# PROB_S7CAS_FLASH-JTAG.net
KiCad netlist of a schematic drawn in Altium Designer
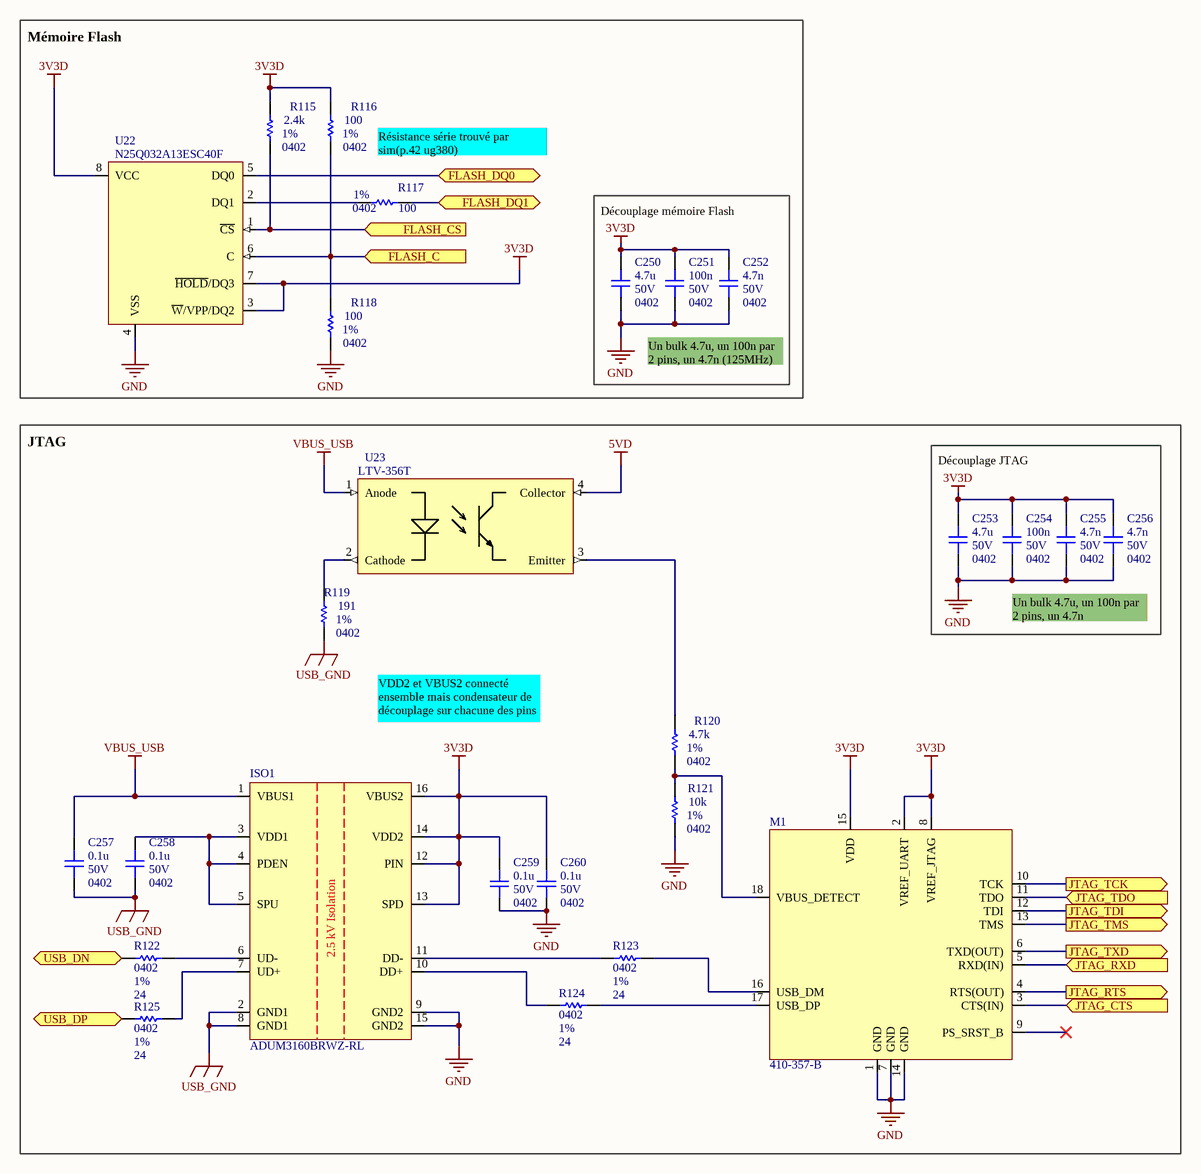
[diagram p0: PROB_S7CAS_FLASH-JTAG.SchDoc]

(export (version "E")
  (design (tool "Eeschema 10.0.6"))
  (components
    (comp (ref "C250")
      (value "4.7u")
      (footprint "CAP_0402")
      (description "CAP - 0402")
      (fields
        (field (name "VOLTAGE") "50V")
        (field (name "PACKAGE") "0402")
        (field (name "CREATEDBY") "Jonathan Bouchard")
      )
      (libsource (lib "S7CAS_LIB2021") (part "CAP - 0402"))
    )
    (comp (ref "C251")
      (value "100n")
      (footprint "CAP_0402")
      (description "CAP - 0402")
      (fields
        (field (name "VOLTAGE") "50V")
        (field (name "PACKAGE") "0402")
        (field (name "CREATEDBY") "Jonathan Bouchard")
      )
      (libsource (lib "S7CAS_LIB2021") (part "CAP - 0402"))
    )
    (comp (ref "C252")
      (value "4.7n")
      (footprint "CAP_0402")
      (description "CAP - 0402")
      (fields
        (field (name "VOLTAGE") "50V")
        (field (name "PACKAGE") "0402")
        (field (name "CREATEDBY") "Jonathan Bouchard")
      )
      (libsource (lib "S7CAS_LIB2021") (part "CAP - 0402"))
    )
    (comp (ref "C253")
      (value "4.7u")
      (footprint "CAP_0402")
      (description "CAP - 0402")
      (fields
        (field (name "VOLTAGE") "50V")
        (field (name "PACKAGE") "0402")
        (field (name "CREATEDBY") "Jonathan Bouchard")
      )
      (libsource (lib "S7CAS_LIB2021") (part "CAP - 0402"))
    )
    (comp (ref "C254")
      (value "100n")
      (footprint "CAP_0402")
      (description "CAP - 0402")
      (fields
        (field (name "VOLTAGE") "50V")
        (field (name "PACKAGE") "0402")
        (field (name "CREATEDBY") "Jonathan Bouchard")
      )
      (libsource (lib "S7CAS_LIB2021") (part "CAP - 0402"))
    )
    (comp (ref "C255")
      (value "4.7n")
      (footprint "CAP_0402")
      (description "CAP - 0402")
      (fields
        (field (name "VOLTAGE") "50V")
        (field (name "PACKAGE") "0402")
        (field (name "CREATEDBY") "Jonathan Bouchard")
      )
      (libsource (lib "S7CAS_LIB2021") (part "CAP - 0402"))
    )
    (comp (ref "C256")
      (value "4.7n")
      (footprint "CAP_0402")
      (description "CAP - 0402")
      (fields
        (field (name "VOLTAGE") "50V")
        (field (name "PACKAGE") "0402")
        (field (name "CREATEDBY") "Jonathan Bouchard")
      )
      (libsource (lib "S7CAS_LIB2021") (part "CAP - 0402"))
    )
    (comp (ref "C257")
      (value "0.1u")
      (footprint "CAP_0402")
      (description "CAP - 0402")
      (fields
        (field (name "VOLTAGE") "50V")
        (field (name "PACKAGE") "0402")
        (field (name "CREATEDBY") "Jonathan Bouchard")
      )
      (libsource (lib "S7CAS_LIB2021") (part "CAP - 0402"))
    )
    (comp (ref "C258")
      (value "0.1u")
      (footprint "CAP_0402")
      (description "CAP - 0402")
      (fields
        (field (name "VOLTAGE") "50V")
        (field (name "PACKAGE") "0402")
        (field (name "CREATEDBY") "Jonathan Bouchard")
      )
      (libsource (lib "S7CAS_LIB2021") (part "CAP - 0402"))
    )
    (comp (ref "C259")
      (value "0.1u")
      (footprint "CAP_0402")
      (description "CAP - 0402")
      (fields
        (field (name "VOLTAGE") "50V")
        (field (name "PACKAGE") "0402")
        (field (name "CREATEDBY") "Jonathan Bouchard")
      )
      (libsource (lib "S7CAS_LIB2021") (part "CAP - 0402"))
    )
    (comp (ref "C260")
      (value "0.1u")
      (footprint "CAP_0402")
      (description "CAP - 0402")
      (fields
        (field (name "VOLTAGE") "50V")
        (field (name "PACKAGE") "0402")
        (field (name "CREATEDBY") "Jonathan Bouchard")
      )
      (libsource (lib "S7CAS_LIB2021") (part "CAP - 0402"))
    )
    (comp (ref "ISO1")
      (value "ADUM3160BRWZ-RL")
      (footprint "ISO_ADUM3160BRWZ-RL")
      (description "ISO - DGTL ISO 2.5KV 2CH USB - 16SOIC")
      (fields
        (field (name "CREATEDBY/DATE") "Tommy Rossignol 2018-11-16")
        (field (name "VERIFIEDBY") "Caroline Paulin - 13 février 2019")
      )
      (libsource (lib "S7CAS_LIB2021") (part "ISO_ADUM3160BRWZ-RL"))
    )
    (comp (ref "M1")
      (value "410-357-B")
      (footprint "MOD_JTAG_410-357-B")
      (description "MOD - JTAG-SMT3-NC Programming Module For Xilinx FPGA - 18-SMT")
      (fields
        (field (name "CREATEDBY/DATE") "Tommy Rossignol 2018-11-23")
        (field (name "VERIFIEDBY") "Nicolas V. (2019-01-28)")
      )
      (libsource (lib "S7CAS_LIB2021") (part "MOD_JTAG_410-357-B"))
    )
    (comp (ref "R115")
      (value "2.4k")
      (footprint "RES_0402")
      (description "RES - 0402")
      (fields
        (field (name "VOLTAGE") "50V")
        (field (name "POWER") "1/16W")
        (field (name "PACKAGE") "0402")
        (field (name "PRECISION") "1%")
        (field (name "CREATEDBY") "Jonathan Bouchard")
      )
      (libsource (lib "S7CAS_LIB2021") (part "RES - 0402"))
    )
    (comp (ref "R116")
      (value "100")
      (footprint "RES_0402")
      (description "RES - 0402")
      (fields
        (field (name "VOLTAGE") "50V")
        (field (name "POWER") "1/16W")
        (field (name "PACKAGE") "0402")
        (field (name "PRECISION") "1%")
        (field (name "CREATEDBY") "Jonathan Bouchard")
      )
      (libsource (lib "S7CAS_LIB2021") (part "RES - 0402"))
    )
    (comp (ref "R117")
      (value "100")
      (footprint "RES_0402")
      (description "RES - 0402")
      (fields
        (field (name "VOLTAGE") "50V")
        (field (name "POWER") "1/16W")
        (field (name "PACKAGE") "0402")
        (field (name "PRECISION") "1%")
        (field (name "CREATEDBY") "Jonathan Bouchard")
      )
      (libsource (lib "S7CAS_LIB2021") (part "RES - 0402"))
    )
    (comp (ref "R118")
      (value "100")
      (footprint "RES_0402")
      (description "RES - 0402")
      (fields
        (field (name "VOLTAGE") "50V")
        (field (name "POWER") "1/16W")
        (field (name "PACKAGE") "0402")
        (field (name "PRECISION") "1%")
        (field (name "CREATEDBY") "Jonathan Bouchard")
      )
      (libsource (lib "S7CAS_LIB2021") (part "RES - 0402"))
    )
    (comp (ref "R119")
      (value "191")
      (footprint "RES_0402")
      (description "RES - 0402")
      (fields
        (field (name "VOLTAGE") "50V")
        (field (name "POWER") "1/16W")
        (field (name "PACKAGE") "0402")
        (field (name "PRECISION") "1%")
        (field (name "CREATEDBY") "Jonathan Bouchard")
      )
      (libsource (lib "S7CAS_LIB2021") (part "RES - 0402"))
    )
    (comp (ref "R120")
      (value "4.7k")
      (footprint "RES_0402")
      (description "RES - 0402")
      (fields
        (field (name "VOLTAGE") "50V")
        (field (name "POWER") "1/16W")
        (field (name "PACKAGE") "0402")
        (field (name "PRECISION") "1%")
        (field (name "CREATEDBY") "Jonathan Bouchard")
      )
      (libsource (lib "S7CAS_LIB2021") (part "RES - 0402"))
    )
    (comp (ref "R121")
      (value "10k")
      (footprint "RES_0402")
      (description "RES - 0402")
      (fields
        (field (name "VOLTAGE") "50V")
        (field (name "POWER") "1/16W")
        (field (name "PACKAGE") "0402")
        (field (name "PRECISION") "1%")
        (field (name "CREATEDBY") "Jonathan Bouchard")
      )
      (libsource (lib "S7CAS_LIB2021") (part "RES - 0402"))
    )
    (comp (ref "R122")
      (value "24")
      (footprint "RES_0402")
      (description "RES - 0402")
      (fields
        (field (name "VOLTAGE") "50V")
        (field (name "POWER") "1/16W")
        (field (name "PACKAGE") "0402")
        (field (name "PRECISION") "1%")
        (field (name "CREATEDBY") "Jonathan Bouchard")
      )
      (libsource (lib "S7CAS_LIB2021") (part "RES - 0402"))
    )
    (comp (ref "R123")
      (value "24")
      (footprint "RES_0402")
      (description "RES - 0402")
      (fields
        (field (name "VOLTAGE") "50V")
        (field (name "POWER") "1/16W")
        (field (name "PACKAGE") "0402")
        (field (name "PRECISION") "1%")
        (field (name "CREATEDBY") "Jonathan Bouchard")
      )
      (libsource (lib "S7CAS_LIB2021") (part "RES - 0402"))
    )
    (comp (ref "R124")
      (value "24")
      (footprint "RES_0402")
      (description "RES - 0402")
      (fields
        (field (name "VOLTAGE") "50V")
        (field (name "POWER") "1/16W")
        (field (name "PACKAGE") "0402")
        (field (name "PRECISION") "1%")
        (field (name "CREATEDBY") "Jonathan Bouchard")
      )
      (libsource (lib "S7CAS_LIB2021") (part "RES - 0402"))
    )
    (comp (ref "R125")
      (value "24")
      (footprint "RES_0402")
      (description "RES - 0402")
      (fields
        (field (name "VOLTAGE") "50V")
        (field (name "POWER") "1/16W")
        (field (name "PACKAGE") "0402")
        (field (name "PRECISION") "1%")
        (field (name "CREATEDBY") "Jonathan Bouchard")
      )
      (libsource (lib "S7CAS_LIB2021") (part "RES - 0402"))
    )
    (comp (ref "U22")
      (value "N25Q032A13ESC40F")
      (footprint "SOIC127P790X216-8N")
      (description "N25Q032A - 32Mb, 3V, Multiple I/O Serial Flash Memory - 8-SOIC (0.209\", 5.30mm Width)")
      (libsource (lib "LIB_TEMP_S7CAS_SCH") (part "IC FLASH 32MBIT SPI 108MHZ 8SO"))
    )
    (comp (ref "U23")
      (value "LTV-356T")
      (footprint "SOP254P700X240-4N")
      (description "LTV-356T - OPTOISOLATOR 3.75KV TRANS - 4-SOP")
      (libsource (lib "LIB_TEMP_S7CAS_SCH") (part "LTV-356T"))
    )
  )
  (nets
    (net (code "1") (name "/FLASH_C") (class "Default")
      (node (ref "R116") (pin "1") (pinfunction "1_1") (pintype "passive"))
      (node (ref "R118") (pin "2") (pinfunction "2_2") (pintype "passive"))
      (node (ref "U22") (pin "6") (pinfunction "C_6") (pintype "input"))
    )
    (net (code "2") (name "/FLASH_CS") (class "Default")
      (node (ref "R115") (pin "1") (pinfunction "1_1") (pintype "passive"))
      (node (ref "U22") (pin "1") (pinfunction "~{CS}_1") (pintype "input"))
    )
    (net (code "3") (name "/FLASH_DQ0") (class "Default")
      (node (ref "U22") (pin "5") (pinfunction "DQ0_5") (pintype "bidirectional"))
    )
    (net (code "4") (name "/FLASH_DQ1") (class "Default")
      (node (ref "R117") (pin "2") (pinfunction "2_2") (pintype "passive"))
    )
    (net (code "5") (name "/JTAG_CTS") (class "Default")
      (node (ref "M1") (pin "3") (pinfunction "CTS(IN)_3") (pintype "passive"))
    )
    (net (code "6") (name "/JTAG_RTS") (class "Default")
      (node (ref "M1") (pin "4") (pinfunction "RTS(OUT)_4") (pintype "passive"))
    )
    (net (code "7") (name "/JTAG_RXD") (class "Default")
      (node (ref "M1") (pin "5") (pinfunction "RXD(IN)_5") (pintype "passive"))
    )
    (net (code "8") (name "/JTAG_TCK") (class "Default")
      (node (ref "M1") (pin "10") (pinfunction "TCK_10") (pintype "passive"))
    )
    (net (code "9") (name "/JTAG_TDI") (class "Default")
      (node (ref "M1") (pin "12") (pinfunction "TDI_12") (pintype "passive"))
    )
    (net (code "10") (name "/JTAG_TDO") (class "Default")
      (node (ref "M1") (pin "11") (pinfunction "TDO_11") (pintype "passive"))
    )
    (net (code "11") (name "/JTAG_TMS") (class "Default")
      (node (ref "M1") (pin "13") (pinfunction "TMS_13") (pintype "passive"))
    )
    (net (code "12") (name "/JTAG_TXD") (class "Default")
      (node (ref "M1") (pin "6") (pinfunction "TXD(OUT)_6") (pintype "passive"))
    )
    (net (code "13") (name "/USB_DN") (class "Default")
      (node (ref "R122") (pin "2") (pinfunction "2_2") (pintype "passive"))
    )
    (net (code "14") (name "/USB_DP") (class "Default")
      (node (ref "R125") (pin "2") (pinfunction "2_2") (pintype "passive"))
    )
    (net (code "15") (name "3V3D") (class "Default")
      (node (ref "C250") (pin "2") (pinfunction "2_2") (pintype "passive"))
      (node (ref "C251") (pin "2") (pinfunction "2_2") (pintype "passive"))
      (node (ref "C252") (pin "2") (pinfunction "2_2") (pintype "passive"))
      (node (ref "C253") (pin "2") (pinfunction "2_2") (pintype "passive"))
      (node (ref "C254") (pin "2") (pinfunction "2_2") (pintype "passive"))
      (node (ref "C255") (pin "2") (pinfunction "2_2") (pintype "passive"))
      (node (ref "C256") (pin "2") (pinfunction "2_2") (pintype "passive"))
      (node (ref "C259") (pin "2") (pinfunction "2_2") (pintype "passive"))
      (node (ref "C260") (pin "2") (pinfunction "2_2") (pintype "passive"))
      (node (ref "ISO1") (pin "12") (pinfunction "PIN_12") (pintype "passive"))
      (node (ref "ISO1") (pin "13") (pinfunction "SPD_13") (pintype "passive"))
      (node (ref "ISO1") (pin "14") (pinfunction "VDD2_14") (pintype "passive"))
      (node (ref "ISO1") (pin "16") (pinfunction "VBUS2_16") (pintype "passive"))
      (node (ref "M1") (pin "15") (pinfunction "VDD_15") (pintype "passive"))
      (node (ref "M1") (pin "2") (pinfunction "VREF_UART_2") (pintype "passive"))
      (node (ref "M1") (pin "8") (pinfunction "VREF_JTAG_8") (pintype "passive"))
      (node (ref "R115") (pin "2") (pinfunction "2_2") (pintype "passive"))
      (node (ref "R116") (pin "2") (pinfunction "2_2") (pintype "passive"))
      (node (ref "U22") (pin "3") (pinfunction "~{W}/VPP/DQ2_3") (pintype "bidirectional"))
      (node (ref "U22") (pin "7") (pinfunction "~{HOLD}/DQ3_7") (pintype "bidirectional"))
      (node (ref "U22") (pin "8") (pinfunction "VCC_8") (pintype "power_in"))
    )
    (net (code "16") (name "5VD") (class "Default")
      (node (ref "U23") (pin "4") (pinfunction "Collector_4") (pintype "input"))
    )
    (net (code "17") (name "GND") (class "Default")
      (node (ref "C250") (pin "1") (pinfunction "1_1") (pintype "passive"))
      (node (ref "C251") (pin "1") (pinfunction "1_1") (pintype "passive"))
      (node (ref "C252") (pin "1") (pinfunction "1_1") (pintype "passive"))
      (node (ref "C253") (pin "1") (pinfunction "1_1") (pintype "passive"))
      (node (ref "C254") (pin "1") (pinfunction "1_1") (pintype "passive"))
      (node (ref "C255") (pin "1") (pinfunction "1_1") (pintype "passive"))
      (node (ref "C256") (pin "1") (pinfunction "1_1") (pintype "passive"))
      (node (ref "C259") (pin "1") (pinfunction "1_1") (pintype "passive"))
      (node (ref "C260") (pin "1") (pinfunction "1_1") (pintype "passive"))
      (node (ref "ISO1") (pin "15") (pinfunction "GND2_15") (pintype "passive"))
      (node (ref "ISO1") (pin "9") (pinfunction "GND2_9") (pintype "passive"))
      (node (ref "M1") (pin "1") (pinfunction "GND_1") (pintype "passive"))
      (node (ref "M1") (pin "14") (pinfunction "GND_14") (pintype "passive"))
      (node (ref "M1") (pin "7") (pinfunction "GND_7") (pintype "passive"))
      (node (ref "R118") (pin "1") (pinfunction "1_1") (pintype "passive"))
      (node (ref "R121") (pin "1") (pinfunction "1_1") (pintype "passive"))
      (node (ref "U22") (pin "4") (pinfunction "VSS_4") (pintype "passive"))
    )
    (net (code "18") (name "Net-(ISO1-DD+)") (class "Default")
      (node (ref "ISO1") (pin "10") (pinfunction "DD+_10") (pintype "passive"))
      (node (ref "R124") (pin "2") (pinfunction "2_2") (pintype "passive"))
    )
    (net (code "19") (name "Net-(ISO1-DD-)") (class "Default")
      (node (ref "ISO1") (pin "11") (pinfunction "DD-_11") (pintype "passive"))
      (node (ref "R123") (pin "2") (pinfunction "2_2") (pintype "passive"))
    )
    (net (code "20") (name "Net-(ISO1-PDEN)") (class "Default")
      (node (ref "C258") (pin "2") (pinfunction "2_2") (pintype "passive"))
      (node (ref "ISO1") (pin "3") (pinfunction "VDD1_3") (pintype "passive"))
      (node (ref "ISO1") (pin "4") (pinfunction "PDEN_4") (pintype "passive"))
      (node (ref "ISO1") (pin "5") (pinfunction "SPU_5") (pintype "passive"))
    )
    (net (code "21") (name "Net-(ISO1-UD+)") (class "Default")
      (node (ref "ISO1") (pin "7") (pinfunction "UD+_7") (pintype "passive"))
      (node (ref "R125") (pin "1") (pinfunction "1_1") (pintype "passive"))
    )
    (net (code "22") (name "Net-(ISO1-UD-)") (class "Default")
      (node (ref "ISO1") (pin "6") (pinfunction "UD-_6") (pintype "passive"))
      (node (ref "R122") (pin "1") (pinfunction "1_1") (pintype "passive"))
    )
    (net (code "23") (name "Net-(M1-USB_DM)") (class "Default")
      (node (ref "M1") (pin "16") (pinfunction "USB_DM_16") (pintype "passive"))
      (node (ref "R123") (pin "1") (pinfunction "1_1") (pintype "passive"))
    )
    (net (code "24") (name "Net-(M1-USB_DP)") (class "Default")
      (node (ref "M1") (pin "17") (pinfunction "USB_DP_17") (pintype "passive"))
      (node (ref "R124") (pin "1") (pinfunction "1_1") (pintype "passive"))
    )
    (net (code "25") (name "Net-(M1-VBUS_DETECT)") (class "Default")
      (node (ref "M1") (pin "18") (pinfunction "VBUS_DETECT_18") (pintype "passive"))
      (node (ref "R120") (pin "1") (pinfunction "1_1") (pintype "passive"))
      (node (ref "R121") (pin "2") (pinfunction "2_2") (pintype "passive"))
    )
    (net (code "26") (name "Net-(U22-DQ1)") (class "Default")
      (node (ref "R117") (pin "1") (pinfunction "1_1") (pintype "passive"))
      (node (ref "U22") (pin "2") (pinfunction "DQ1_2") (pintype "bidirectional"))
    )
    (net (code "27") (name "Net-(U23-Cathode)") (class "Default")
      (node (ref "R119") (pin "2") (pinfunction "2_2") (pintype "passive"))
      (node (ref "U23") (pin "2") (pinfunction "Cathode_2") (pintype "output"))
    )
    (net (code "28") (name "Net-(U23-Emitter)") (class "Default")
      (node (ref "R120") (pin "2") (pinfunction "2_2") (pintype "passive"))
      (node (ref "U23") (pin "3") (pinfunction "Emitter_3") (pintype "output"))
    )
    (net (code "29") (name "USB_GND") (class "Default")
      (node (ref "C257") (pin "1") (pinfunction "1_1") (pintype "passive"))
      (node (ref "C258") (pin "1") (pinfunction "1_1") (pintype "passive"))
      (node (ref "ISO1") (pin "2") (pinfunction "GND1_2") (pintype "passive"))
      (node (ref "ISO1") (pin "8") (pinfunction "GND1_8") (pintype "passive"))
      (node (ref "R119") (pin "1") (pinfunction "1_1") (pintype "passive"))
    )
    (net (code "30") (name "VBUS_USB") (class "Default")
      (node (ref "C257") (pin "2") (pinfunction "2_2") (pintype "passive"))
      (node (ref "ISO1") (pin "1") (pinfunction "VBUS1_1") (pintype "passive"))
      (node (ref "U23") (pin "1") (pinfunction "Anode_1") (pintype "input"))
    )
    (net (code "31") (name "unconnected-(M1-PS_SRST_B-Pad9)") (class "Default")
      (node (ref "M1") (pin "9") (pinfunction "PS_SRST_B_9") (pintype "passive+no_connect"))
    )
  )
)
